# SBH_BMS.net
KiCad netlist of a schematic drawn in Altium Designer
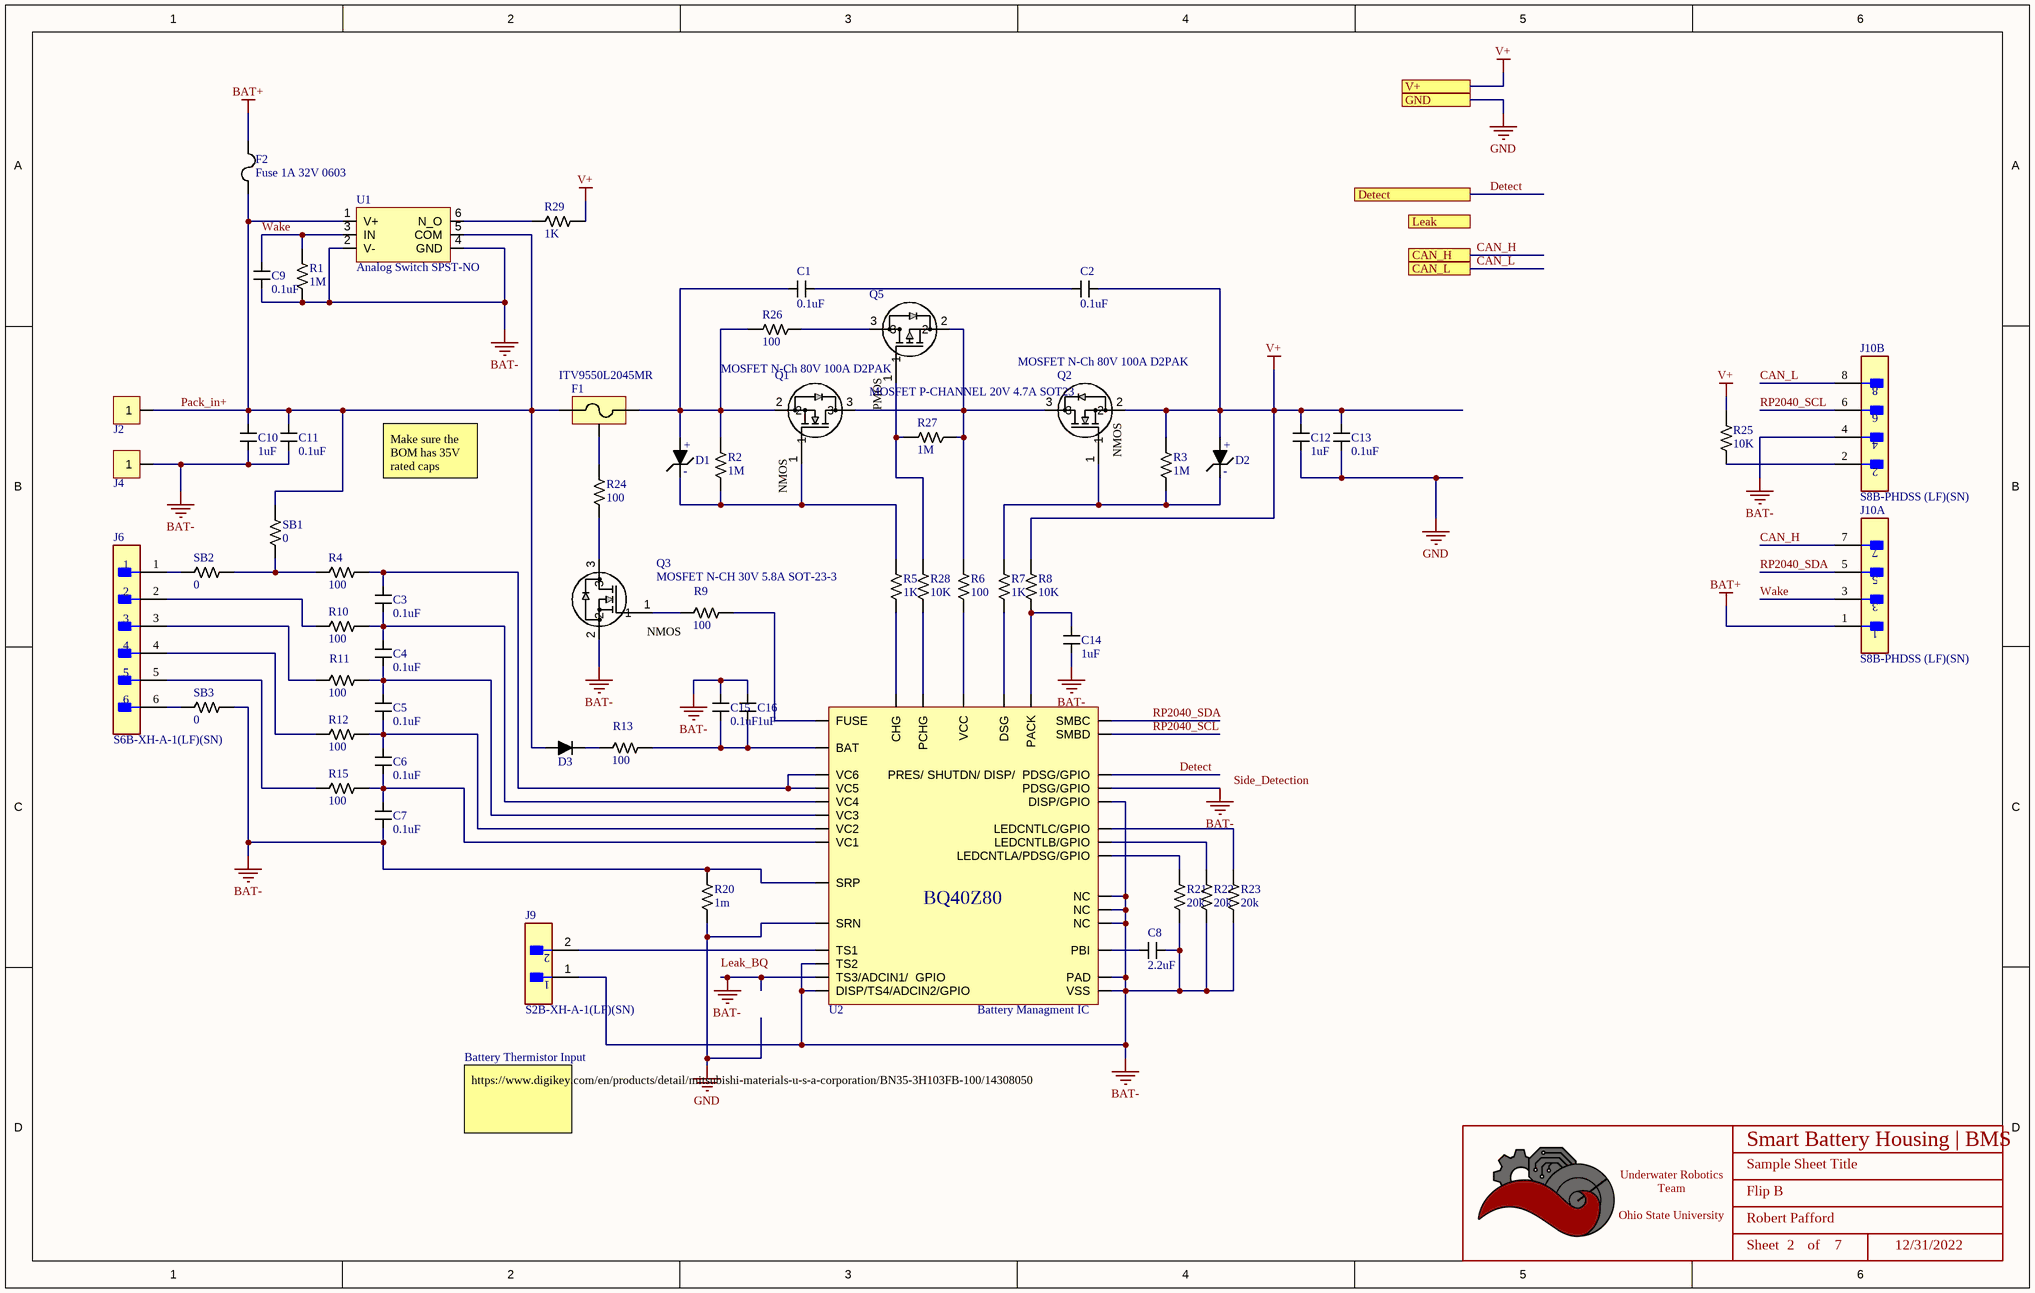
[diagram p0: SBH_BMS.SchDoc]

(export (version "E")
  (design (tool "Eeschema 10.0.6"))
  (components
    (comp (ref "C1")
      (value "0.1uF")
      (footprint "CAPACITOR_0402")
      (description "Cap 100nF 25V +/-10%\r\nCeramic 0402")
      (fields
        (field (name "TOLERANCE") "+/- 10%")
        (field (name "VOLTAGE") "25V")
        (field (name "MADE BY") "Robert Pafford")
      )
      (libsource (lib "Capacitors") (part "CAPACITOR_0.1uF_0402"))
    )
    (comp (ref "C2")
      (value "0.1uF")
      (footprint "CAPACITOR_0402")
      (description "Cap 100nF 25V +/-10%\r\nCeramic 0402")
      (fields
        (field (name "TOLERANCE") "+/- 10%")
        (field (name "VOLTAGE") "25V")
        (field (name "MADE BY") "Robert Pafford")
      )
      (libsource (lib "Capacitors") (part "CAPACITOR_0.1uF_0402"))
    )
    (comp (ref "C3")
      (value "0.1uF")
      (footprint "CAPACITOR_0402")
      (description "Cap 100nF 25V +/-10%\r\nCeramic 0402")
      (fields
        (field (name "TOLERANCE") "+/- 10%")
        (field (name "VOLTAGE") "25V")
        (field (name "MADE BY") "Robert Pafford")
      )
      (libsource (lib "Capacitors") (part "CAPACITOR_0.1uF_0402"))
    )
    (comp (ref "C4")
      (value "0.1uF")
      (footprint "CAPACITOR_0402")
      (description "Cap 100nF 25V +/-10%\r\nCeramic 0402")
      (fields
        (field (name "TOLERANCE") "+/- 10%")
        (field (name "VOLTAGE") "25V")
        (field (name "MADE BY") "Robert Pafford")
      )
      (libsource (lib "Capacitors") (part "CAPACITOR_0.1uF_0402"))
    )
    (comp (ref "C5")
      (value "0.1uF")
      (footprint "CAPACITOR_0402")
      (description "Cap 100nF 25V +/-10%\r\nCeramic 0402")
      (fields
        (field (name "TOLERANCE") "+/- 10%")
        (field (name "VOLTAGE") "25V")
        (field (name "MADE BY") "Robert Pafford")
      )
      (libsource (lib "Capacitors") (part "CAPACITOR_0.1uF_0402"))
    )
    (comp (ref "C6")
      (value "0.1uF")
      (footprint "CAPACITOR_0402")
      (description "Cap 100nF 25V +/-10%\r\nCeramic 0402")
      (fields
        (field (name "TOLERANCE") "+/- 10%")
        (field (name "VOLTAGE") "25V")
        (field (name "MADE BY") "Robert Pafford")
      )
      (libsource (lib "Capacitors") (part "CAPACITOR_0.1uF_0402"))
    )
    (comp (ref "C7")
      (value "0.1uF")
      (footprint "CAPACITOR_0402")
      (description "Cap 100nF 25V +/-10%\r\nCeramic 0402")
      (fields
        (field (name "TOLERANCE") "+/- 10%")
        (field (name "VOLTAGE") "25V")
        (field (name "MADE BY") "Robert Pafford")
      )
      (libsource (lib "Capacitors") (part "CAPACITOR_0.1uF_0402"))
    )
    (comp (ref "C8")
      (value "2.2uF")
      (footprint "CAPACITOR_0402")
      (description "Cap 2.2uF 35V +/-10%\r\nCeramic 0402")
      (fields
        (field (name "TOLERANCE") "+/- 10%")
        (field (name "VOLTAGE") "35V")
        (field (name "MADE BY") "Flip B")
      )
      (libsource (lib "Capacitors") (part "CAPACITOR_2.2uF_0402"))
    )
    (comp (ref "C9")
      (value "0.1uF")
      (footprint "CAPACITOR_0402")
      (description "Cap 100nF 25V +/-10%\r\nCeramic 0402")
      (fields
        (field (name "TOLERANCE") "+/- 10%")
        (field (name "VOLTAGE") "25V")
        (field (name "MADE BY") "Robert Pafford")
      )
      (libsource (lib "Capacitors") (part "CAPACITOR_0.1uF_0402"))
    )
    (comp (ref "C10")
      (value "1uF")
      (footprint "CAPACITOR_0402")
      (description "Cap 1uF 16V +/-10%\r\nCeramic 0402")
      (fields
        (field (name "TOLERANCE") "+/- 10%")
        (field (name "VOLTAGE") "16V")
        (field (name "MADE BY") "Robert Pafford")
      )
      (libsource (lib "Capacitors") (part "CAPACITOR_1uF_0402"))
    )
    (comp (ref "C11")
      (value "0.1uF")
      (footprint "CAPACITOR_0402")
      (description "Cap 100nF 25V +/-10%\r\nCeramic 0402")
      (fields
        (field (name "TOLERANCE") "+/- 10%")
        (field (name "VOLTAGE") "25V")
        (field (name "MADE BY") "Robert Pafford")
      )
      (libsource (lib "Capacitors") (part "CAPACITOR_0.1uF_0402"))
    )
    (comp (ref "C12")
      (value "1uF")
      (footprint "CAPACITOR_0402")
      (description "Cap 1uF 16V +/-10%\r\nCeramic 0402")
      (fields
        (field (name "TOLERANCE") "+/- 10%")
        (field (name "VOLTAGE") "16V")
        (field (name "MADE BY") "Robert Pafford")
      )
      (libsource (lib "Capacitors") (part "CAPACITOR_1uF_0402"))
    )
    (comp (ref "C13")
      (value "0.1uF")
      (footprint "CAPACITOR_0402")
      (description "Cap 100nF 25V +/-10%\r\nCeramic 0402")
      (fields
        (field (name "TOLERANCE") "+/- 10%")
        (field (name "VOLTAGE") "25V")
        (field (name "MADE BY") "Robert Pafford")
      )
      (libsource (lib "Capacitors") (part "CAPACITOR_0.1uF_0402"))
    )
    (comp (ref "C14")
      (value "1uF")
      (footprint "CAPACITOR_0402")
      (description "Cap 1uF 16V +/-10%\r\nCeramic 0402")
      (fields
        (field (name "TOLERANCE") "+/- 10%")
        (field (name "VOLTAGE") "16V")
        (field (name "MADE BY") "Robert Pafford")
      )
      (libsource (lib "Capacitors") (part "CAPACITOR_1uF_0402"))
    )
    (comp (ref "C15")
      (value "0.1uF")
      (footprint "CAPACITOR_0402")
      (description "Cap 100nF 25V +/-10%\r\nCeramic 0402")
      (fields
        (field (name "TOLERANCE") "+/- 10%")
        (field (name "VOLTAGE") "25V")
        (field (name "MADE BY") "Robert Pafford")
      )
      (libsource (lib "Capacitors") (part "CAPACITOR_0.1uF_0402"))
    )
    (comp (ref "C16")
      (value "1uF")
      (footprint "CAPACITOR_0402")
      (description "Cap 1uF 16V +/-10%\r\nCeramic 0402")
      (fields
        (field (name "TOLERANCE") "+/- 10%")
        (field (name "VOLTAGE") "16V")
        (field (name "MADE BY") "Robert Pafford")
      )
      (libsource (lib "Capacitors") (part "CAPACITOR_1uF_0402"))
    )
    (comp (ref "D1")
      (value "Zener_Diode_16V_500mW")
      (footprint "SOD-123")
      (description "Zener Diode ¦ 16 V ¦ 500 mW ¦ SOD-123")
      (fields (field (name "POWER") "500mW") (field (name "MADE BY") "Flip B"))
      (libsource (lib "Diodes") (part "Zener_Diode_16V_500mW"))
    )
    (comp (ref "D2")
      (value "Zener_Diode_16V_500mW")
      (footprint "SOD-123")
      (description "Zener Diode ¦ 16 V ¦ 500 mW ¦ SOD-123")
      (fields (field (name "POWER") "500mW") (field (name "MADE BY") "Flip B"))
      (libsource (lib "Diodes") (part "Zener_Diode_16V_500mW"))
    )
    (comp (ref "D3")
      (value "MBR0520LT3G")
      (footprint "SOD-123")
      (description "Schottky Diode, 20V reverse breakdown, 500mA, Vf = 0.385V")
      (fields (field (name "MADE BY") "Flip B"))
      (libsource (lib "Diodes") (part "SCHOTTKY_20V_500mA"))
    )
    (comp (ref "F1")
      (value "ITV9550L2045MR")
      (footprint "ITV9550")
      (description "LittelFuse  ¦ 45A ¦ 5S ¦ SMD ¦ Self-Control Protector")
      (fields (field (name "CREATED BY") "Flip B"))
      (libsource (lib "Fuses") (part "ITV9550L2045MR"))
    )
    (comp (ref "F2")
      (value "Fuse 1A 32V 0603")
      (footprint "2-SMD Fuse 0603")
      (description "Pansonic ¦ 32V ¦ 1A ¦ 0603 ¦ Fast Blow")
      (fields
        (field (name "MANUFACTURER_PART_NUMBER") "ERB-RE1R00V")
        (field (name "CREATED BY") "Nathan Ayer")
      )
      (libsource (lib "Fuses") (part "ERB-RE1R00V"))
    )
    (comp (ref "J2")
      (value "Redcube M4 Term 85A")
      (footprint "Redcube M4 Term 85A")
      (fields (field (name "CREATED BY") "Nahtan Ayer"))
      (libsource (lib "Connectors") (part "Redcube M4 Term 85A"))
    )
    (comp (ref "J4")
      (value "Redcube M4 Term 85A")
      (footprint "Redcube M4 Term 85A")
      (fields (field (name "CREATED BY") "Nahtan Ayer"))
      (libsource (lib "Connectors") (part "Redcube M4 Term 85A"))
    )
    (comp (ref "J6")
      (value "S6B-XH-A-1(LF)(SN)")
      (footprint "FP-S6B-XH-A-1_LF_SN-MFG")
      (description "CONN HEADER R/A P6OS 2.5MM")
      (libsource (lib "Altium Content Vault") (part "f2cb566baf1c37ab5a3b8e90bbeafd6"))
    )
    (comp (ref "J9")
      (value "S2B-XH-A-1(LF)(SN)")
      (footprint "FP-S2B-XH-A-1_LF_SN-MFG")
      (description "CONN HEADER R/A 2POS 2.5MM")
      (libsource (lib "Altium Content Vault") (part "3bc925449376181038e59eaffc5286c"))
    )
    (comp (ref "J10")
      (value "S8B-PHDSS (LF)(SN)")
      (footprint "FP-S8B-PHDSS_LF_SN-MFG")
      (description "CONN HEADER R/A 8POS 2MM")
      (libsource (lib "Altium Content Vault") (part "811e954b9c034aa737de4d9295cbe7e"))
    )
    (comp (ref "Q1")
      (value "MOSFET N-Ch 80V 100A D2PAK")
      (footprint "D2PAK")
      (description "N-Channel 80V 100A (Ta) 306W (Ta), Surface Mount D2PAK")
      (fields
        (field (name "MANUFACTURER _PART_NUMBER") "PSMN4R4-80BS,118")
        (field (name "CREATED BY") "Flip B")
      )
      (libsource (lib "Transistors") (part "PSMN4R4-80BS,118"))
    )
    (comp (ref "Q2")
      (value "MOSFET N-Ch 80V 100A D2PAK")
      (footprint "D2PAK")
      (description "N-Channel 80V 100A (Ta) 306W (Ta), Surface Mount D2PAK")
      (fields
        (field (name "MANUFACTURER _PART_NUMBER") "PSMN4R4-80BS,118")
        (field (name "CREATED BY") "Flip B")
      )
      (libsource (lib "Transistors") (part "PSMN4R4-80BS,118"))
    )
    (comp (ref "Q3")
      (value "MOSFET N-CH 30V 5.8A SOT-23-3")
      (footprint "SOT-23-3")
      (description "N-Channel 30 V 5.8A (Ta) 1.4W (Ta) Surface Mount SOT-23-3")
      (fields (field (name "MANUFACTURER _PART_NUMBER") "AO3404A") (field (name "CREATED BY") "Dylan T"))
      (libsource (lib "Transistors") (part "AO3404A"))
    )
    (comp (ref "Q5")
      (value "MOSFET P-CHANNEL 20V 4.7A SOT23")
      (footprint "SOT-23-3")
      (description "P-Channel 20 V 4.7A (Tc) 1.56W (Tc) Surface Mount SOT-23")
      (fields
        (field (name "MANUFACTURER_PART_NUMBER") "TSM500P02CX")
        (field (name "CREATED BY") "Robert Pafford")
      )
      (libsource (lib "Transistors") (part "TSM500P02CX"))
    )
    (comp (ref "R1")
      (value "1M")
      (footprint "RESISTOR_0603")
      (description "RES 1M OHM 1/8W 0603")
      (fields
        (field (name "TOLERANCE") "+/- 5%")
        (field (name "VALUE  (OHMS)") "1M")
        (field (name "MADE BY") "Robert Pafford")
      )
      (libsource (lib "Resistors") (part "RESISTOR_1M_0603"))
    )
    (comp (ref "R2")
      (value "1M")
      (footprint "RESISTOR_0603")
      (description "RES 1M OHM 1/8W 0603")
      (fields
        (field (name "TOLERANCE") "+/- 5%")
        (field (name "VALUE  (OHMS)") "1M")
        (field (name "MADE BY") "Robert Pafford")
      )
      (libsource (lib "Resistors") (part "RESISTOR_1M_0603"))
    )
    (comp (ref "R3")
      (value "1M")
      (footprint "RESISTOR_0603")
      (description "RES 1M OHM 1/8W 0603")
      (fields
        (field (name "TOLERANCE") "+/- 5%")
        (field (name "VALUE  (OHMS)") "1M")
        (field (name "MADE BY") "Robert Pafford")
      )
      (libsource (lib "Resistors") (part "RESISTOR_1M_0603"))
    )
    (comp (ref "R4")
      (value "100 Ohm 5% 1/16W")
      (footprint "RESISTOR_0402")
      (description "RES 100 OHM 5% 1/16W 0402")
      (fields
        (field (name "TOLERANCE") "+/- 5%")
        (field (name "VALUE  (OHMS)") "100")
        (field (name "MADE BY") "Flip B")
      )
      (libsource (lib "Resistors") (part "RESISTOR_100_0402"))
    )
    (comp (ref "R5")
      (value "1k Ohm 1% 1/16W")
      (footprint "RESISTOR_0402")
      (description "RES 1k OHM 1% 1/16W 0402")
      (fields
        (field (name "TOLERANCE") "+/- 1%")
        (field (name "VALUE  (OHMS)") "1K")
        (field (name "MADE BY") "Robert Pafford")
      )
      (libsource (lib "Resistors") (part "RESISTOR_1K_0402"))
    )
    (comp (ref "R6")
      (value "100 Ohm 5% 1/16W")
      (footprint "RESISTOR_0402")
      (description "RES 100 OHM 5% 1/16W 0402")
      (fields
        (field (name "TOLERANCE") "+/- 5%")
        (field (name "VALUE  (OHMS)") "100")
        (field (name "MADE BY") "Flip B")
      )
      (libsource (lib "Resistors") (part "RESISTOR_100_0402"))
    )
    (comp (ref "R7")
      (value "1k Ohm 1% 1/16W")
      (footprint "RESISTOR_0402")
      (description "RES 1k OHM 1% 1/16W 0402")
      (fields
        (field (name "TOLERANCE") "+/- 1%")
        (field (name "VALUE  (OHMS)") "1K")
        (field (name "MADE BY") "Robert Pafford")
      )
      (libsource (lib "Resistors") (part "RESISTOR_1K_0402"))
    )
    (comp (ref "R8")
      (value "10k Ohm 1% 1/16W")
      (footprint "RESISTOR_0402")
      (description "RES 10k OHM 1% 1/16W 0402")
      (fields
        (field (name "TOLERANCE") "+/- 1%")
        (field (name "VALUE  (OHMS)") "10K")
        (field (name "MADE BY") "Robert Pafford")
      )
      (libsource (lib "Resistors") (part "RESISTOR_10K_0402"))
    )
    (comp (ref "R9")
      (value "100 Ohm 5% 1/16W")
      (footprint "RESISTOR_0402")
      (description "RES 100 OHM 5% 1/16W 0402")
      (fields
        (field (name "TOLERANCE") "+/- 5%")
        (field (name "VALUE  (OHMS)") "100")
        (field (name "MADE BY") "Flip B")
      )
      (libsource (lib "Resistors") (part "RESISTOR_100_0402"))
    )
    (comp (ref "R10")
      (value "100 Ohm 5% 1/16W")
      (footprint "RESISTOR_0402")
      (description "RES 100 OHM 5% 1/16W 0402")
      (fields
        (field (name "TOLERANCE") "+/- 5%")
        (field (name "VALUE  (OHMS)") "100")
        (field (name "MADE BY") "Flip B")
      )
      (libsource (lib "Resistors") (part "RESISTOR_100_0402"))
    )
    (comp (ref "R11")
      (value "100 Ohm 5% 1/16W")
      (footprint "RESISTOR_0402")
      (description "RES 100 OHM 5% 1/16W 0402")
      (fields
        (field (name "TOLERANCE") "+/- 5%")
        (field (name "VALUE  (OHMS)") "100")
        (field (name "MADE BY") "Flip B")
      )
      (libsource (lib "Resistors") (part "RESISTOR_100_0402"))
    )
    (comp (ref "R12")
      (value "100 Ohm 5% 1/16W")
      (footprint "RESISTOR_0402")
      (description "RES 100 OHM 5% 1/16W 0402")
      (fields
        (field (name "TOLERANCE") "+/- 5%")
        (field (name "VALUE  (OHMS)") "100")
        (field (name "MADE BY") "Flip B")
      )
      (libsource (lib "Resistors") (part "RESISTOR_100_0402"))
    )
    (comp (ref "R13")
      (value "100 Ohm 5% 1/16W")
      (footprint "RESISTOR_0402")
      (description "RES 100 OHM 5% 1/16W 0402")
      (fields
        (field (name "TOLERANCE") "+/- 5%")
        (field (name "VALUE  (OHMS)") "100")
        (field (name "MADE BY") "Flip B")
      )
      (libsource (lib "Resistors") (part "RESISTOR_100_0402"))
    )
    (comp (ref "R15")
      (value "100 Ohm 5% 1/16W")
      (footprint "RESISTOR_0402")
      (description "RES 100 OHM 5% 1/16W 0402")
      (fields
        (field (name "TOLERANCE") "+/- 5%")
        (field (name "VALUE  (OHMS)") "100")
        (field (name "MADE BY") "Flip B")
      )
      (libsource (lib "Resistors") (part "RESISTOR_100_0402"))
    )
    (comp (ref "R20")
      (value "1m Ohm 5% 8W")
      (footprint "RES_CSS2H-3920")
      (description "RES 1m OHM 1% 8W Current Sense")
      (fields
        (field (name "TOLERANCE") "+/- 1%")
        (field (name "VALUE  (OHMS)") "1m")
        (field (name "MADE BY") "Flip B")
      )
      (libsource (lib "Resistors") (part "RESISTOR_1m_CS"))
    )
    (comp (ref "R21")
      (value "20k Ohm 1% 1/16W")
      (footprint "RESISTOR_0402")
      (description "RES 20k OHM 1% 1/16W 0402")
      (fields
        (field (name "TOLERANCE") "+/- 1%")
        (field (name "VALUE  (OHMS)") "20k")
        (field (name "MADE BY") "Flip B")
      )
      (libsource (lib "Resistors") (part "RESISTOR_20K_0402"))
    )
    (comp (ref "R22")
      (value "20k Ohm 1% 1/16W")
      (footprint "RESISTOR_0402")
      (description "RES 20k OHM 1% 1/16W 0402")
      (fields
        (field (name "TOLERANCE") "+/- 1%")
        (field (name "VALUE  (OHMS)") "20k")
        (field (name "MADE BY") "Flip B")
      )
      (libsource (lib "Resistors") (part "RESISTOR_20K_0402"))
    )
    (comp (ref "R23")
      (value "20k Ohm 1% 1/16W")
      (footprint "RESISTOR_0402")
      (description "RES 20k OHM 1% 1/16W 0402")
      (fields
        (field (name "TOLERANCE") "+/- 1%")
        (field (name "VALUE  (OHMS)") "20k")
        (field (name "MADE BY") "Flip B")
      )
      (libsource (lib "Resistors") (part "RESISTOR_20K_0402"))
    )
    (comp (ref "R24")
      (value "100 Ohm 5% 1/16W")
      (footprint "RESISTOR_0402")
      (description "RES 100 OHM 5% 1/16W 0402")
      (fields
        (field (name "TOLERANCE") "+/- 5%")
        (field (name "VALUE  (OHMS)") "100")
        (field (name "MADE BY") "Flip B")
      )
      (libsource (lib "Resistors") (part "RESISTOR_100_0402"))
    )
    (comp (ref "R25")
      (value "10k Ohm 5% 1/10W")
      (footprint "RESISTOR_0603")
      (description "RES 10k OHM 5% 1/10W 0603")
      (fields
        (field (name "TOLERANCE") "+/- 5%")
        (field (name "VALUE  (OHMS)") "10K")
        (field (name "MADE BY") "Robert Pafford")
      )
      (libsource (lib "Resistors") (part "RESISTOR_10K_0603"))
    )
    (comp (ref "R26")
      (value "100 Ohm 5% 1/16W")
      (footprint "RESISTOR_0402")
      (description "RES 100 OHM 5% 1/16W 0402")
      (fields
        (field (name "TOLERANCE") "+/- 5%")
        (field (name "VALUE  (OHMS)") "100")
        (field (name "MADE BY") "Flip B")
      )
      (libsource (lib "Resistors") (part "RESISTOR_100_0402"))
    )
    (comp (ref "R27")
      (value "1M")
      (footprint "RESISTOR_0603")
      (description "RES 1M OHM 1/8W 0603")
      (fields
        (field (name "TOLERANCE") "+/- 5%")
        (field (name "VALUE  (OHMS)") "1M")
        (field (name "MADE BY") "Robert Pafford")
      )
      (libsource (lib "Resistors") (part "RESISTOR_1M_0603"))
    )
    (comp (ref "R28")
      (value "10k Ohm 1% 1/16W")
      (footprint "RESISTOR_0402")
      (description "RES 10k OHM 1% 1/16W 0402")
      (fields
        (field (name "TOLERANCE") "+/- 1%")
        (field (name "VALUE  (OHMS)") "10K")
        (field (name "MADE BY") "Robert Pafford")
      )
      (libsource (lib "Resistors") (part "RESISTOR_10K_0402"))
    )
    (comp (ref "R29")
      (value "1k Ohm 5% 1/8W")
      (footprint "RESISTOR_0603")
      (description "RES 1k OHM 5% 1/8W 0603")
      (fields
        (field (name "TOLERANCE") "+/- 5%")
        (field (name "VALUE  (OHMS)") "1K")
        (field (name "MADE BY") "Robert Pafford")
      )
      (libsource (lib "Resistors") (part "RESISTOR_1K_0603"))
    )
    (comp (ref "SB1")
      (value "0 Ohm Jumper No Fit")
      (footprint "RESISTOR_0603")
      (description "0 Ohm Jumper No Fit for Solder Bridge")
      (fields (field (name "VALUE  (OHMS)") "0") (field (name "MADE BY") "Robert Pafford"))
      (libsource (lib "Resistors") (part "JUMPER_0_0603"))
    )
    (comp (ref "SB2")
      (value "0 Ohm Jumper No Fit")
      (footprint "RESISTOR_0603")
      (description "0 Ohm Jumper No Fit for Solder Bridge")
      (fields (field (name "VALUE  (OHMS)") "0") (field (name "MADE BY") "Robert Pafford"))
      (libsource (lib "Resistors") (part "JUMPER_0_0603"))
    )
    (comp (ref "SB3")
      (value "0 Ohm Jumper No Fit")
      (footprint "RESISTOR_0603")
      (description "0 Ohm Jumper No Fit for Solder Bridge")
      (fields (field (name "VALUE  (OHMS)") "0") (field (name "MADE BY") "Robert Pafford"))
      (libsource (lib "Resistors") (part "JUMPER_0_0603"))
    )
    (comp (ref "U1")
      (value "Analog Switch SPST-NO")
      (footprint "TSOT-23_S6")
      (description "Analog Switch SPST Normally Open")
      (fields
        (field (name "MF") "Analog Devices")
        (field (name "VOLTAGE") "9-36V")
        (field (name "CREATED BY") "Flip B")
      )
      (libsource (lib "Integrated Circuits") (part "MAX4520EUT+T"))
    )
    (comp (ref "U2")
      (value "Battery Managment IC")
      (footprint "VQFN-32")
      (description "Multifuntion Li-ion/ Lipo Battery Pack Managment IC")
      (fields
        (field (name "MANUFACTURER") "Texas Instruments")
        (field (name "PARTNUMBER") "BQ40Z80RSMT")
        (field (name "CREATED BY") "Flip B")
      )
      (libsource (lib "Integrated Circuits") (part "BQ40Z80RSMT"))
    )
  )
  (nets
    (net (code "1") (name "/CAN_H") (class "Default")
      (node (ref "J10") (pin "7") (pinfunction "7_7") (pintype "passive"))
    )
    (net (code "2") (name "/CAN_L") (class "Default")
      (node (ref "J10") (pin "8") (pinfunction "8_8") (pintype "passive"))
    )
    (net (code "3") (name "/Detect") (class "Default")
      (node (ref "U2") (pin "17") (pinfunction "PRES/_SHUTDN/_DISP/__PDSG/GPIO_17") (pintype "passive"))
    )
    (net (code "6") (name "/Pack_in+") (class "Default")
      (node (ref "C10") (pin "1") (pinfunction "1_1") (pintype "passive"))
      (node (ref "C11") (pin "1") (pinfunction "1_1") (pintype "passive"))
      (node (ref "D3") (pin "1") (pinfunction "1_1") (pintype "passive"))
      (node (ref "F1") (pin "2") (pinfunction "2_2") (pintype "passive"))
      (node (ref "F2") (pin "1") (pinfunction "1_1") (pintype "passive"))
      (node (ref "J2") (pin "1") (pinfunction "1_1") (pintype "passive"))
      (node (ref "SB1") (pin "1") (pinfunction "1_1") (pintype "passive"))
      (node (ref "U1") (pin "1") (pinfunction "V+_1") (pintype "passive"))
      (node (ref "U1") (pin "5") (pinfunction "COM_5") (pintype "passive"))
    )
    (net (code "7") (name "/RP2040_SCL") (class "Default")
      (node (ref "J10") (pin "6") (pinfunction "6_6") (pintype "passive"))
      (node (ref "U2") (pin "18") (pinfunction "SMBD_18") (pintype "passive"))
    )
    (net (code "8") (name "/RP2040_SDA") (class "Default")
      (node (ref "J10") (pin "5") (pinfunction "5_5") (pintype "passive"))
      (node (ref "U2") (pin "19") (pinfunction "SMBC_19") (pintype "passive"))
    )
    (net (code "10") (name "/Wake") (class "Default")
      (node (ref "C9") (pin "1") (pinfunction "1_1") (pintype "passive"))
      (node (ref "J10") (pin "3") (pinfunction "3_3") (pintype "passive"))
      (node (ref "R1") (pin "1") (pinfunction "1_1") (pintype "passive"))
      (node (ref "U1") (pin "3") (pinfunction "IN_3") (pintype "passive"))
    )
    (net (code "11") (name "BAT+") (class "Default")
      (node (ref "F2") (pin "2") (pinfunction "2_2") (pintype "passive"))
      (node (ref "J10") (pin "1") (pinfunction "1_1") (pintype "passive"))
    )
    (net (code "12") (name "BAT-") (class "Default")
      (node (ref "C10") (pin "2") (pinfunction "2_2") (pintype "passive"))
      (node (ref "C11") (pin "2") (pinfunction "2_2") (pintype "passive"))
      (node (ref "C14") (pin "2") (pinfunction "2_2") (pintype "passive"))
      (node (ref "C15") (pin "1") (pinfunction "1_1") (pintype "passive"))
      (node (ref "C16") (pin "1") (pinfunction "1_1") (pintype "passive"))
      (node (ref "C7") (pin "2") (pinfunction "2_2") (pintype "passive"))
      (node (ref "C8") (pin "1") (pinfunction "1_1") (pintype "passive"))
      (node (ref "C9") (pin "2") (pinfunction "2_2") (pintype "passive"))
      (node (ref "J10") (pin "4") (pinfunction "4_4") (pintype "passive"))
      (node (ref "J4") (pin "1") (pinfunction "1_1") (pintype "passive"))
      (node (ref "J9") (pin "1") (pinfunction "1_1") (pintype "passive"))
      (node (ref "Q3") (pin "2") (pinfunction "2_2") (pintype "passive"))
      (node (ref "R1") (pin "2") (pinfunction "2_2") (pintype "passive"))
      (node (ref "R20") (pin "1") (pinfunction "1_1") (pintype "passive"))
      (node (ref "R21") (pin "2") (pinfunction "2_2") (pintype "passive"))
      (node (ref "R22") (pin "2") (pinfunction "2_2") (pintype "passive"))
      (node (ref "R23") (pin "2") (pinfunction "2_2") (pintype "passive"))
      (node (ref "SB3") (pin "1") (pinfunction "1_1") (pintype "passive"))
      (node (ref "U1") (pin "2") (pinfunction "V-_2") (pintype "power_in"))
      (node (ref "U1") (pin "4") (pinfunction "GND_4") (pintype "passive"))
      (node (ref "U2") (pin "11") (pinfunction "TS2_11") (pintype "passive"))
      (node (ref "U2") (pin "12") (pinfunction "TS3/ADCIN1/__GPIO_12") (pintype "passive"))
      (node (ref "U2") (pin "13") (pinfunction "DISP/TS4/ADCIN2/GPIO_13") (pintype "passive"))
      (node (ref "U2") (pin "14") (pinfunction "NC_14") (pintype "passive"))
      (node (ref "U2") (pin "15") (pinfunction "DISP/GPIO_15") (pintype "passive"))
      (node (ref "U2") (pin "16") (pinfunction "PDSG/GPIO_16") (pintype "passive"))
      (node (ref "U2") (pin "27") (pinfunction "NC_27") (pintype "passive"))
      (node (ref "U2") (pin "33") (pinfunction "PAD_33") (pintype "passive"))
      (node (ref "U2") (pin "7") (pinfunction "NC_7") (pintype "passive"))
      (node (ref "U2") (pin "8") (pinfunction "SRP_8") (pintype "passive"))
      (node (ref "U2") (pin "9") (pinfunction "VSS_9") (pintype "passive"))
    )
    (net (code "13") (name "GND") (class "Default")
      (node (ref "C12") (pin "2") (pinfunction "2_2") (pintype "passive"))
      (node (ref "C13") (pin "2") (pinfunction "2_2") (pintype "passive"))
      (node (ref "R20") (pin "2") (pinfunction "2_2") (pintype "passive"))
      (node (ref "U2") (pin "6") (pinfunction "SRN_6") (pintype "passive"))
    )
    (net (code "14") (name "Net-(C1-Pad1)") (class "Default")
      (node (ref "C1") (pin "1") (pinfunction "1_1") (pintype "passive"))
      (node (ref "C2") (pin "2") (pinfunction "2_2") (pintype "passive"))
    )
    (net (code "15") (name "Net-(C1-Pad2)") (class "Default")
      (node (ref "C1") (pin "2") (pinfunction "2_2") (pintype "passive"))
      (node (ref "D1") (pin "1") (pinfunction "1_1") (pintype "passive"))
      (node (ref "F1") (pin "1") (pinfunction "1_1") (pintype "passive"))
      (node (ref "Q1") (pin "2") (pinfunction "2_2") (pintype "passive"))
      (node (ref "R2") (pin "1") (pinfunction "1_1") (pintype "passive"))
      (node (ref "R26") (pin "1") (pinfunction "1_1") (pintype "passive"))
    )
    (net (code "16") (name "Net-(D1-Pad2)") (class "Default")
      (node (ref "D1") (pin "2") (pinfunction "2_2") (pintype "passive"))
      (node (ref "Q1") (pin "1") (pinfunction "1_1") (pintype "passive"))
      (node (ref "R2") (pin "2") (pinfunction "2_2") (pintype "passive"))
      (node (ref "R5") (pin "1") (pinfunction "1_1") (pintype "passive"))
    )
    (net (code "17") (name "Net-(D2-Pad2)") (class "Default")
      (node (ref "D2") (pin "2") (pinfunction "2_2") (pintype "passive"))
      (node (ref "Q2") (pin "1") (pinfunction "1_1") (pintype "passive"))
      (node (ref "R3") (pin "2") (pinfunction "2_2") (pintype "passive"))
      (node (ref "R7") (pin "1") (pinfunction "1_1") (pintype "passive"))
    )
    (net (code "18") (name "Net-(D3-Pad2)") (class "Default")
      (node (ref "D3") (pin "2") (pinfunction "2_2") (pintype "passive"))
      (node (ref "R13") (pin "2") (pinfunction "2_2") (pintype "passive"))
    )
    (net (code "19") (name "Net-(F1-Pad3)") (class "Default")
      (node (ref "F1") (pin "3") (pinfunction "3_3") (pintype "passive"))
      (node (ref "R24") (pin "1") (pinfunction "1_1") (pintype "passive"))
    )
    (net (code "20") (name "Net-(J6-Pad1)") (class "Default")
      (node (ref "J6") (pin "1") (pinfunction "1_1") (pintype "passive"))
      (node (ref "SB2") (pin "2") (pinfunction "2_2") (pintype "passive"))
    )
    (net (code "21") (name "Net-(J6-Pad2)") (class "Default")
      (node (ref "J6") (pin "2") (pinfunction "2_2") (pintype "passive"))
      (node (ref "R10") (pin "2") (pinfunction "2_2") (pintype "passive"))
    )
    (net (code "22") (name "Net-(J6-Pad3)") (class "Default")
      (node (ref "J6") (pin "3") (pinfunction "3_3") (pintype "passive"))
      (node (ref "R11") (pin "2") (pinfunction "2_2") (pintype "passive"))
    )
    (net (code "23") (name "Net-(J6-Pad4)") (class "Default")
      (node (ref "J6") (pin "4") (pinfunction "4_4") (pintype "passive"))
      (node (ref "R12") (pin "2") (pinfunction "2_2") (pintype "passive"))
    )
    (net (code "24") (name "Net-(J6-Pad5)") (class "Default")
      (node (ref "J6") (pin "5") (pinfunction "5_5") (pintype "passive"))
      (node (ref "R15") (pin "2") (pinfunction "2_2") (pintype "passive"))
    )
    (net (code "25") (name "Net-(J6-Pad6)") (class "Default")
      (node (ref "J6") (pin "6") (pinfunction "6_6") (pintype "passive"))
      (node (ref "SB3") (pin "2") (pinfunction "2_2") (pintype "passive"))
    )
    (net (code "26") (name "Net-(J10-Pad2)") (class "Default")
      (node (ref "J10") (pin "2") (pinfunction "2_2") (pintype "passive"))
      (node (ref "R25") (pin "2") (pinfunction "2_2") (pintype "passive"))
    )
    (net (code "27") (name "Net-(Q1-Pad3)") (class "Default")
      (node (ref "Q1") (pin "3") (pinfunction "3_3") (pintype "passive"))
      (node (ref "Q2") (pin "3") (pinfunction "3_3") (pintype "passive"))
      (node (ref "Q5") (pin "2") (pinfunction "2_2") (pintype "passive"))
      (node (ref "R27") (pin "2") (pinfunction "2_2") (pintype "passive"))
      (node (ref "R6") (pin "1") (pinfunction "1_1") (pintype "passive"))
    )
    (net (code "28") (name "Net-(Q3-Pad1)") (class "Default")
      (node (ref "Q3") (pin "1") (pinfunction "1_1") (pintype "passive"))
      (node (ref "R9") (pin "2") (pinfunction "2_2") (pintype "passive"))
    )
    (net (code "29") (name "Net-(Q3-Pad3)") (class "Default")
      (node (ref "Q3") (pin "3") (pinfunction "3_3") (pintype "passive"))
      (node (ref "R24") (pin "2") (pinfunction "2_2") (pintype "passive"))
    )
    (net (code "30") (name "Net-(Q5-Pad1)") (class "Default")
      (node (ref "Q5") (pin "1") (pinfunction "1_1") (pintype "passive"))
      (node (ref "R27") (pin "1") (pinfunction "1_1") (pintype "passive"))
      (node (ref "R28") (pin "1") (pinfunction "1_1") (pintype "passive"))
    )
    (net (code "31") (name "Net-(Q5-Pad3)") (class "Default")
      (node (ref "Q5") (pin "3") (pinfunction "3_3") (pintype "passive"))
      (node (ref "R26") (pin "2") (pinfunction "2_2") (pintype "passive"))
    )
    (net (code "32") (name "Net-(R4-Pad2)") (class "Default")
      (node (ref "R4") (pin "2") (pinfunction "2_2") (pintype "passive"))
      (node (ref "SB1") (pin "2") (pinfunction "2_2") (pintype "passive"))
      (node (ref "SB2") (pin "1") (pinfunction "1_1") (pintype "passive"))
    )
    (net (code "33") (name "Net-(U1-N_O)") (class "Default")
      (node (ref "R29") (pin "2") (pinfunction "2_2") (pintype "passive"))
      (node (ref "U1") (pin "6") (pinfunction "N_O_6") (pintype "passive"))
    )
    (net (code "34") (name "Net-(U2-BAT)") (class "Default")
      (node (ref "C15") (pin "2") (pinfunction "2_2") (pintype "passive"))
      (node (ref "C16") (pin "2") (pinfunction "2_2") (pintype "passive"))
      (node (ref "R13") (pin "1") (pinfunction "1_1") (pintype "passive"))
      (node (ref "U2") (pin "30") (pinfunction "BAT_30") (pintype "passive"))
    )
    (net (code "35") (name "Net-(U2-CHG)") (class "Default")
      (node (ref "R5") (pin "2") (pinfunction "2_2") (pintype "passive"))
      (node (ref "U2") (pin "29") (pinfunction "CHG_29") (pintype "passive"))
    )
    (net (code "36") (name "Net-(U2-DSG)") (class "Default")
      (node (ref "R7") (pin "2") (pinfunction "2_2") (pintype "passive"))
      (node (ref "U2") (pin "26") (pinfunction "DSG_26") (pintype "passive"))
    )
    (net (code "37") (name "Net-(U2-FUSE)") (class "Default")
      (node (ref "R9") (pin "1") (pinfunction "1_1") (pintype "passive"))
      (node (ref "U2") (pin "23") (pinfunction "FUSE_23") (pintype "passive"))
    )
    (net (code "38") (name "Net-(U2-LEDCNTLA{slash}PDSG{slash}GPIO)") (class "Default")
      (node (ref "R21") (pin "1") (pinfunction "1_1") (pintype "passive"))
      (node (ref "U2") (pin "20") (pinfunction "LEDCNTLA/PDSG/GPIO_20") (pintype "passive"))
    )
    (net (code "39") (name "Net-(U2-LEDCNTLB{slash}GPIO)") (class "Default")
      (node (ref "R22") (pin "1") (pinfunction "1_1") (pintype "passive"))
      (node (ref "U2") (pin "21") (pinfunction "LEDCNTLB/GPIO_21") (pintype "passive"))
    )
    (net (code "40") (name "Net-(U2-LEDCNTLC{slash}GPIO)") (class "Default")
      (node (ref "R23") (pin "1") (pinfunction "1_1") (pintype "passive"))
      (node (ref "U2") (pin "22") (pinfunction "LEDCNTLC/GPIO_22") (pintype "passive"))
    )
    (net (code "41") (name "Net-(U2-PACK)") (class "Default")
      (node (ref "C14") (pin "1") (pinfunction "1_1") (pintype "passive"))
      (node (ref "R8") (pin "2") (pinfunction "2_2") (pintype "passive"))
      (node (ref "U2") (pin "25") (pinfunction "PACK_25") (pintype "passive"))
    )
    (net (code "42") (name "Net-(U2-PBI)") (class "Default")
      (node (ref "C8") (pin "2") (pinfunction "2_2") (pintype "passive"))
      (node (ref "U2") (pin "31") (pinfunction "PBI_31") (pintype "passive"))
    )
    (net (code "43") (name "Net-(U2-PCHG)") (class "Default")
      (node (ref "R28") (pin "2") (pinfunction "2_2") (pintype "passive"))
      (node (ref "U2") (pin "28") (pinfunction "PCHG_28") (pintype "passive"))
    )
    (net (code "44") (name "Net-(U2-TS1)") (class "Default")
      (node (ref "J9") (pin "2") (pinfunction "2_2") (pintype "passive"))
      (node (ref "U2") (pin "10") (pinfunction "TS1_10") (pintype "passive"))
    )
    (net (code "45") (name "Net-(U2-VC1)") (class "Default")
      (node (ref "C6") (pin "2") (pinfunction "2_2") (pintype "passive"))
      (node (ref "C7") (pin "1") (pinfunction "1_1") (pintype "passive"))
      (node (ref "R15") (pin "1") (pinfunction "1_1") (pintype "passive"))
      (node (ref "U2") (pin "5") (pinfunction "VC1_5") (pintype "passive"))
    )
    (net (code "46") (name "Net-(U2-VC2)") (class "Default")
      (node (ref "C5") (pin "2") (pinfunction "2_2") (pintype "passive"))
      (node (ref "C6") (pin "1") (pinfunction "1_1") (pintype "passive"))
      (node (ref "R12") (pin "1") (pinfunction "1_1") (pintype "passive"))
      (node (ref "U2") (pin "4") (pinfunction "VC2_4") (pintype "passive"))
    )
    (net (code "47") (name "Net-(U2-VC3)") (class "Default")
      (node (ref "C4") (pin "2") (pinfunction "2_2") (pintype "passive"))
      (node (ref "C5") (pin "1") (pinfunction "1_1") (pintype "passive"))
      (node (ref "R11") (pin "1") (pinfunction "1_1") (pintype "passive"))
      (node (ref "U2") (pin "3") (pinfunction "VC3_3") (pintype "passive"))
    )
    (net (code "48") (name "Net-(U2-VC4)") (class "Default")
      (node (ref "C3") (pin "2") (pinfunction "2_2") (pintype "passive"))
      (node (ref "C4") (pin "1") (pinfunction "1_1") (pintype "passive"))
      (node (ref "R10") (pin "1") (pinfunction "1_1") (pintype "passive"))
      (node (ref "U2") (pin "2") (pinfunction "VC4_2") (pintype "passive"))
    )
    (net (code "49") (name "Net-(U2-VC5)") (class "Default")
      (node (ref "C3") (pin "1") (pinfunction "1_1") (pintype "passive"))
      (node (ref "R4") (pin "1") (pinfunction "1_1") (pintype "passive"))
      (node (ref "U2") (pin "1") (pinfunction "VC5_1") (pintype "passive"))
      (node (ref "U2") (pin "32") (pinfunction "VC6_32") (pintype "passive"))
    )
    (net (code "50") (name "Net-(U2-VCC)") (class "Default")
      (node (ref "R6") (pin "2") (pinfunction "2_2") (pintype "passive"))
      (node (ref "U2") (pin "24") (pinfunction "VCC_24") (pintype "passive"))
    )
    (net (code "51") (name "V+") (class "Default")
      (node (ref "C12") (pin "1") (pinfunction "1_1") (pintype "passive"))
      (node (ref "C13") (pin "1") (pinfunction "1_1") (pintype "passive"))
      (node (ref "C2") (pin "1") (pinfunction "1_1") (pintype "passive"))
      (node (ref "D2") (pin "1") (pinfunction "1_1") (pintype "passive"))
      (node (ref "Q2") (pin "2") (pinfunction "2_2") (pintype "passive"))
      (node (ref "R25") (pin "1") (pinfunction "1_1") (pintype "passive"))
      (node (ref "R29") (pin "1") (pinfunction "1_1") (pintype "passive"))
      (node (ref "R3") (pin "1") (pinfunction "1_1") (pintype "passive"))
      (node (ref "R8") (pin "1") (pinfunction "1_1") (pintype "passive"))
    )
  )
)
